# LCD.net
KiCad netlist of a schematic drawn in Altium Designer
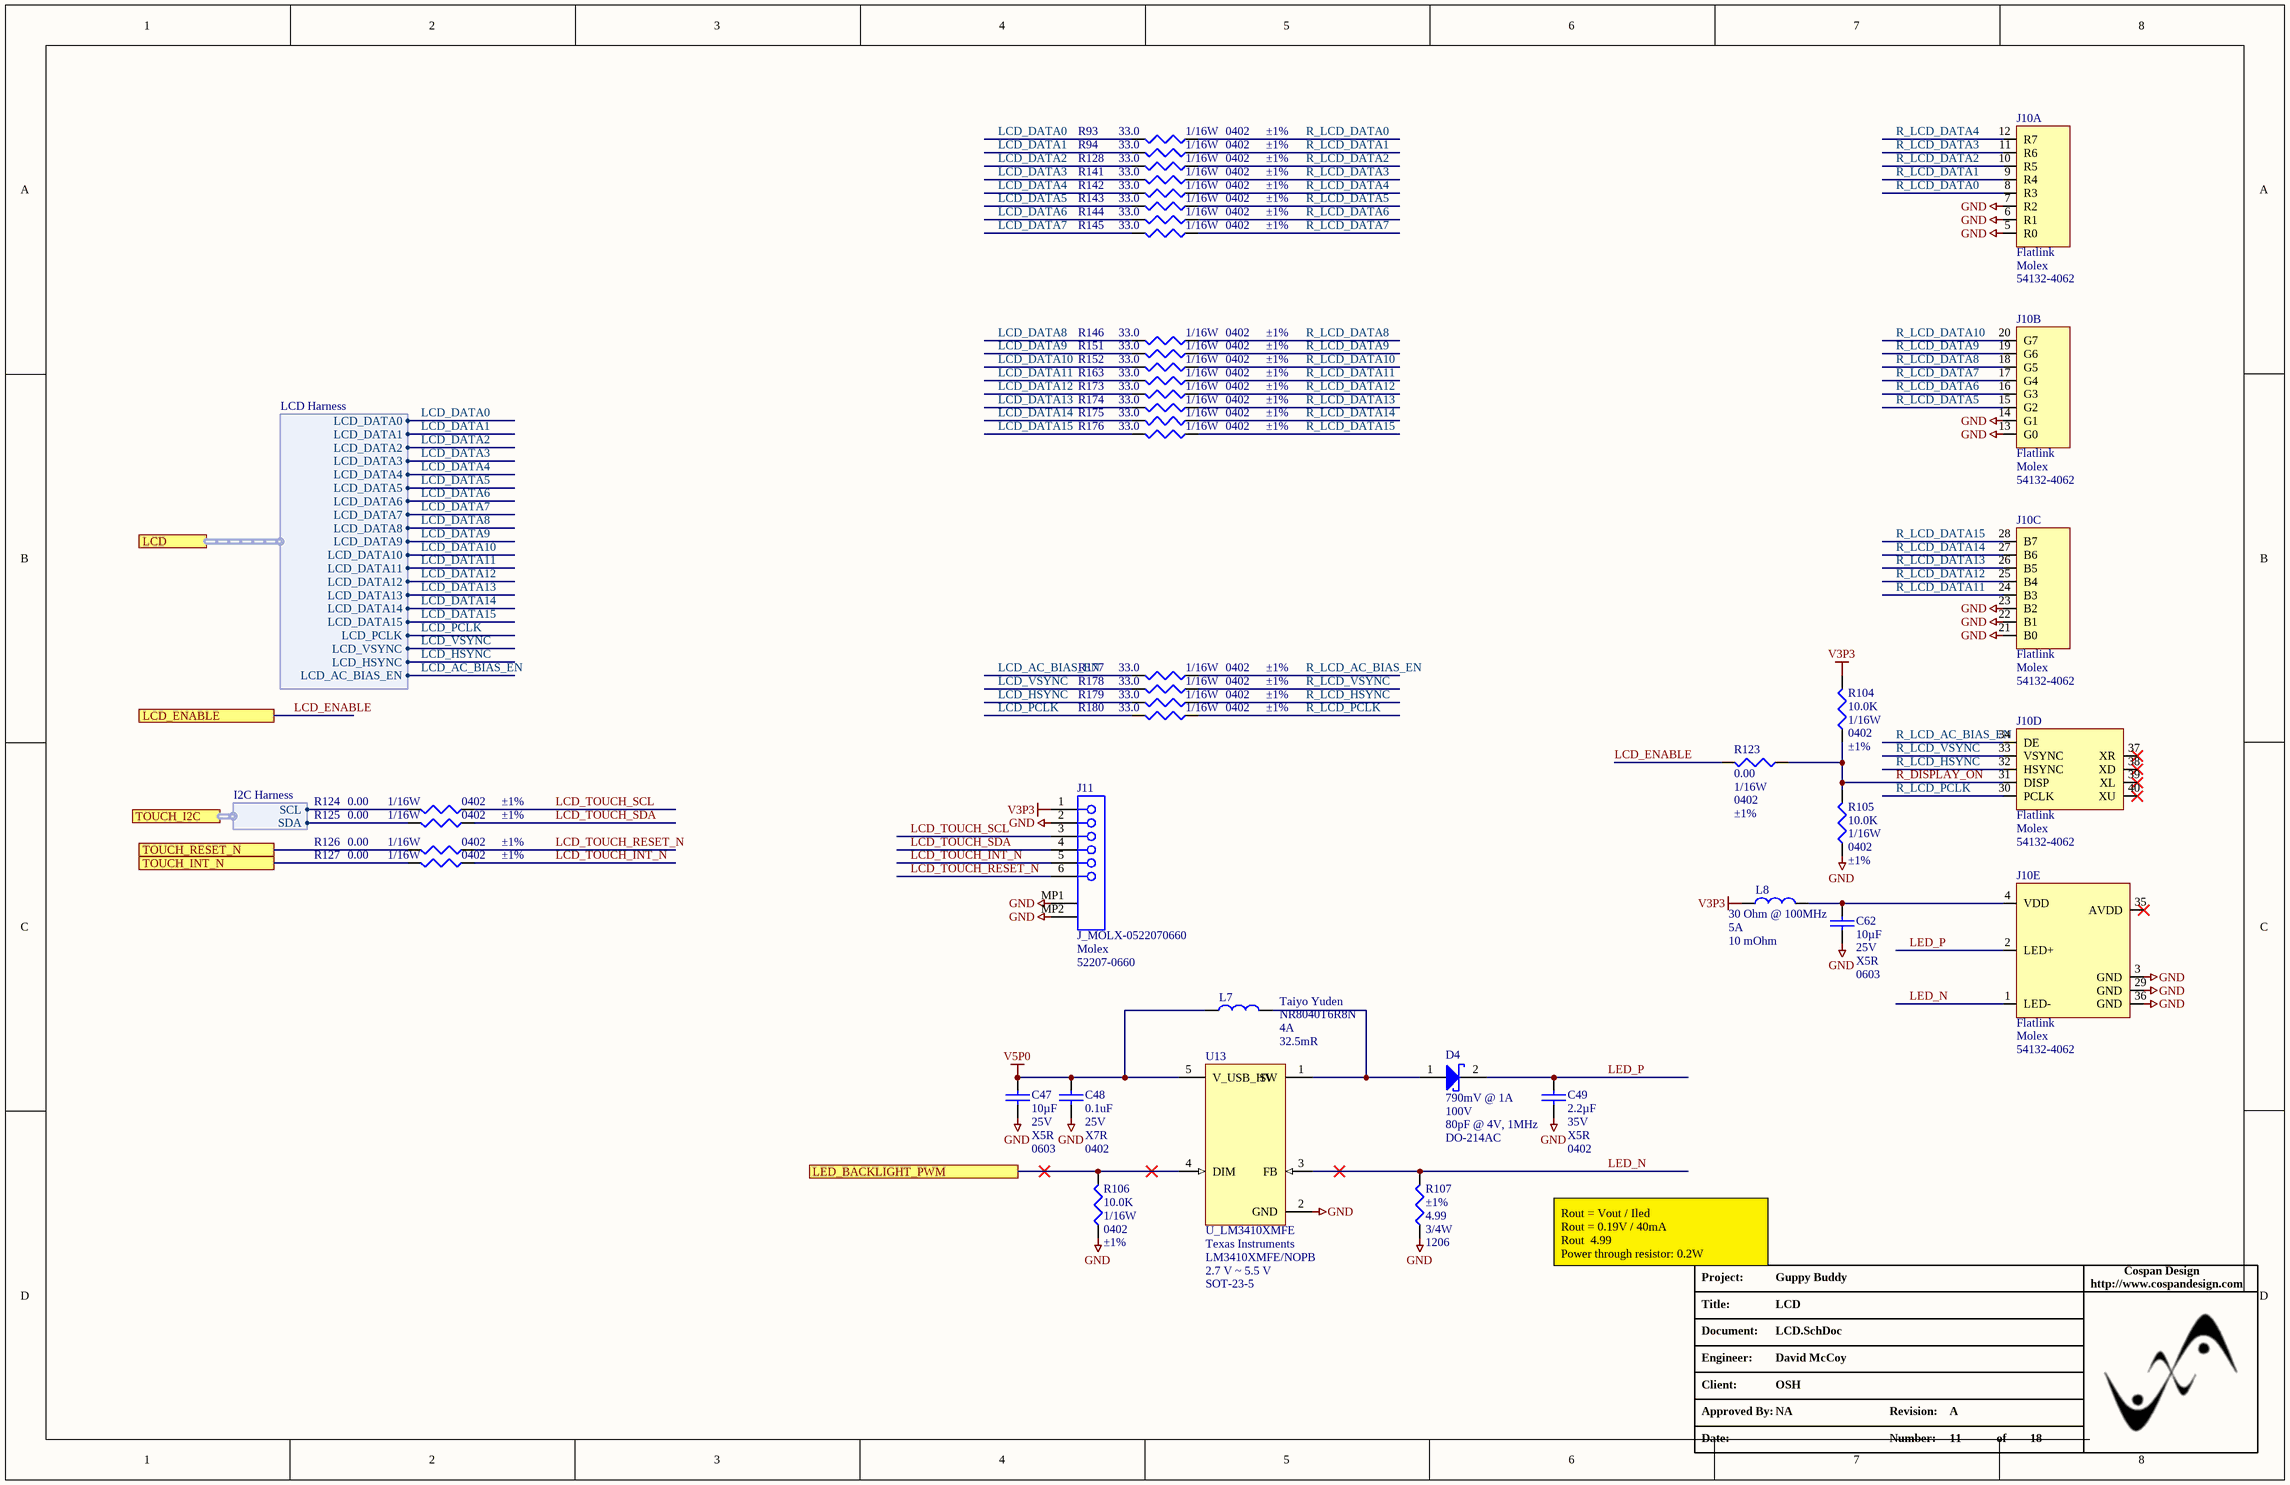
[diagram p0: LCD.SchDoc]

(export (version "E")
  (design (tool "Eeschema 10.0.6"))
  (components
    (comp (ref "C47")
      (value "C_0603_10µF")
      (footprint "C_ERA-0603")
      (description "CAP CER 10UF 16V X5R 0603")
      (fields
        (field (name "CAPACITANCE") "10µF")
        (field (name "VOLTAGE - RATED") "25V")
        (field (name "TEMPERATURE COEFFICIENT") "X5R")
        (field (name "PACKAGE / CASE") "0603")
        (field (name "MANUFACTURER") "Murata Electronics North America")
        (field (name "MANUFACTURER PART NUMBER") "GRM188R61C106MA73D")
      )
      (libsource (lib "Cospan Design") (part "C_0603_10µF"))
    )
    (comp (ref "C48")
      (value "C_0402_0.1UF_25V")
      (footprint "C_0402")
      (description "CAP CER 0.1UF 25V X6S 0402")
      (fields
        (field (name "TOLERANCE") "10%")
        (field (name "CAPACITANCE") "0.1uF")
        (field (name "VOLTAGE - RATED") "25V")
        (field (name "TEMPERATURE COEFFICIENT") "X7R")
        (field (name "PACKAGE / CASE") "0402")
      )
      (libsource (lib "Cospan Design") (part "C_0402_0.1UF_25V"))
    )
    (comp (ref "C49")
      (value "C_0402_2.2uF_35V")
      (footprint "C_0402")
      (description "CAP CER 2.2UF 35V 20% X5R 0402")
      (fields
        (field (name "MANUFACTURER") "TDK Corporation")
        (field (name "MANUFACTURER PART NUMBER") "C1005X5R1V225K050BC")
        (field (name "CAPACITANCE") "2.2µF")
        (field (name "VOLTAGE - RATED") "35V")
        (field (name "TEMPERATURE COEFFICIENT") "X5R")
        (field (name "PACKAGE / CASE") "0402")
      )
      (libsource (lib "Main LibraryX") (part "C_0402_2.2uF_35V"))
    )
    (comp (ref "C62")
      (value "C_0603_10µF")
      (footprint "C_ERA-0603")
      (description "CAP CER 10UF 16V X5R 0603")
      (fields
        (field (name "CAPACITANCE") "10µF")
        (field (name "VOLTAGE - RATED") "25V")
        (field (name "TEMPERATURE COEFFICIENT") "X5R")
        (field (name "PACKAGE / CASE") "0603")
        (field (name "MANUFACTURER") "Murata Electronics North America")
        (field (name "MANUFACTURER PART NUMBER") "GRM188R61C106MA73D")
      )
      (libsource (lib "Cospan Design") (part "C_0603_10µF"))
    )
    (comp (ref "D4")
      (value "B1100-13-F")
      (footprint "DIOM5226X23L")
      (description "DIODE SCHOTTKY 100V 1A SMA")
      (fields
        (field (name "MANUFACTURER") "Diodes Inc")
        (field (name "VOLTAGE - FORWARD (VF) (MAX) @ IF") "790mV @ 1A")
        (field (name "VOLTAGE - DC REVERSE (VR) (MAX)") "100V")
        (field (name "CAPACITANCE @ VR, F") "80pF @ 4V, 1MHz")
        (field (name "PACKAGE / CASE") "DO-214AC")
      )
      (libsource (lib "Main Library") (part "D_SCHOTT_B1100-13-F"))
    )
    (comp (ref "J10")
      (value "Flatlink")
      (footprint "FPC_40PIN_BOTTOM")
      (description "CONN FFC/FPC .50MM 40POS R/A SMD")
      (fields
        (field (name "MANUFACTURER 1") "Molex")
        (field (name "MANUFACTURER PART NUMBER 1") "54132-4062")
      )
      (libsource (lib "Main LibraryX") (part "J_FPC_MOLEX_40POS"))
    )
    (comp (ref "J11")
      (value "J_MOLX-0522070660")
      (footprint "MOLX-52271-0679")
      (description "CONN FFC FPC TOP 6POS 1.00MM R/A")
      (fields
        (field (name "MANUFACTURER 1") "Molex")
        (field (name "MANUFACTURER PART NUMBER 1") "52207-0660")
      )
      (libsource (lib "Main Library") (part "J_MOLX-0522070660"))
    )
    (comp (ref "L7")
      (value "L_6.8µH_SHLD_4A")
      (footprint "IND_TAIYO_NR8040")
      (description "FIXED IND 6.8UH 3.7A 32.5 MOHM")
      (fields
        (field (name "TOLERANCE") "30%")
        (field (name "MANUFACTURER") "Taiyo Yuden")
        (field (name "MANUFACTURER PART NUMBER") "NR8040T6R8N")
        (field (name "MAX DC CURRENT") "4A")
        (field (name "DC RESISTANCE (DCR)") "32.5mR")
      )
      (libsource (lib "Cospan Design") (part "L_6.8µH_SHLD_4A"))
    )
    (comp (ref "L8")
      (value "L_BEAD_0603_30OHM_100MHZ")
      (footprint "R_0603")
      (description "FERRITE BEAD 30 OHM 0603")
      (fields
        (field (name "MANUFACTURER") "TDK Corporation")
        (field (name "MANUFACTURER PART NUMBER") "MPZ1608S300ATAH0")
        (field (name "IMPEDANCE @ FREQUENCY") "30 Ohm @ 100MHz")
        (field (name "CURRENT RATING (MAX)") "5A")
        (field (name "DC RESISTANCE (DCR) (MAX)") "10 mOhm")
      )
      (libsource (lib "Cospan Design") (part "L_BEAD_0603_30OHM_100MHZ"))
    )
    (comp (ref "R93")
      (value "R_0402_33")
      (footprint "R_0402")
      (description "RES 33.0 OHM 1/16W 1% 0402 SMD")
      (fields
        (field (name "MANUFACTURER") "Yageo")
        (field (name "MANUFACTURER PART NUMBER") "RC0402FR-0733RL")
        (field (name "RESISTANCE IN OHMS") "33.0")
        (field (name "POWER (WATTS)") "1/16W")
        (field (name "CASE") "0402")
        (field (name "TOLERANCE") "±1%")
      )
      (libsource (lib "Main Library") (part "R_0402_33"))
    )
    (comp (ref "R94")
      (value "R_0402_33")
      (footprint "R_0402")
      (description "RES 33.0 OHM 1/16W 1% 0402 SMD")
      (fields
        (field (name "MANUFACTURER") "Yageo")
        (field (name "MANUFACTURER PART NUMBER") "RC0402FR-0733RL")
        (field (name "RESISTANCE IN OHMS") "33.0")
        (field (name "POWER (WATTS)") "1/16W")
        (field (name "CASE") "0402")
        (field (name "TOLERANCE") "±1%")
      )
      (libsource (lib "Main Library") (part "R_0402_33"))
    )
    (comp (ref "R104")
      (value "R_0402_10.0K")
      (footprint "R_0402")
      (description "RES 10.0K OHM 1/16W 1% 0402 SMD")
      (fields
        (field (name "MANUFACTURER") "Stackpole Electronics Inc")
        (field (name "MANUFACTURER PART NUMBER") "RMCF0402FT10K0")
        (field (name "RESISTANCE IN OHMS") "10.0K")
        (field (name "POWER (WATTS)") "1/16W")
        (field (name "CASE") "0402")
        (field (name "TOLERANCE") "±1%")
      )
      (libsource (lib "Cospan Design") (part "R_0402_10.0K"))
    )
    (comp (ref "R105")
      (value "R_0402_10.0K")
      (footprint "R_0402")
      (description "RES 10.0K OHM 1/16W 1% 0402 SMD")
      (fields
        (field (name "MANUFACTURER") "Stackpole Electronics Inc")
        (field (name "MANUFACTURER PART NUMBER") "RMCF0402FT10K0")
        (field (name "RESISTANCE IN OHMS") "10.0K")
        (field (name "POWER (WATTS)") "1/16W")
        (field (name "CASE") "0402")
        (field (name "TOLERANCE") "±1%")
      )
      (libsource (lib "Cospan Design") (part "R_0402_10.0K"))
    )
    (comp (ref "R106")
      (value "R_0402_10.0K")
      (footprint "R_0402")
      (description "RES 10.0K OHM 1/16W 1% 0402 SMD")
      (fields
        (field (name "MANUFACTURER") "Stackpole Electronics Inc")
        (field (name "MANUFACTURER PART NUMBER") "RMCF0402FT10K0")
        (field (name "RESISTANCE IN OHMS") "10.0K")
        (field (name "POWER (WATTS)") "1/16W")
        (field (name "CASE") "0402")
        (field (name "TOLERANCE") "±1%")
      )
      (libsource (lib "Cospan Design") (part "R_0402_10.0K"))
    )
    (comp (ref "R107")
      (value "R_1206_4.99")
      (footprint "R_1206")
      (description "RES SMD 4.99 OHM 1% 3/4W 1206")
      (fields
        (field (name "MANUFACTURER") "Vishay / Dale")
        (field (name "MANUFACTURER PART NUMBER") "CRCW12064R99FKEAHP")
        (field (name "TOLERANCE") "±1%")
        (field (name "RESISTANCE IN OHMS") "4.99")
        (field (name "POWER (WATTS)") "3/4W")
        (field (name "CASE") "1206")
      )
      (libsource (lib "Cospan Design") (part "R_1206_4.99"))
    )
    (comp (ref "R123")
      (value "0.0 Ohms")
      (footprint "R_0402")
      (description "RES 0.00 OHM 1/16W 1% 0402 SMD")
      (fields
        (field (name "MANUFACTURER") "Yageo")
        (field (name "MANUFACTURER PART NUMBER") "RC0402JR-070RL")
        (field (name "RESISTANCE IN OHMS") "0.00")
        (field (name "POWER (WATTS)") "1/16W")
        (field (name "CASE") "0402")
        (field (name "TOLERANCE") "±1%")
      )
      (libsource (lib "Cospan Design") (part "R_0402_0.00"))
    )
    (comp (ref "R124")
      (value "0.0 Ohms")
      (footprint "R_0402")
      (description "RES 0.00 OHM 1/16W 1% 0402 SMD")
      (fields
        (field (name "MANUFACTURER") "Yageo")
        (field (name "MANUFACTURER PART NUMBER") "RC0402JR-070RL")
        (field (name "RESISTANCE IN OHMS") "0.00")
        (field (name "POWER (WATTS)") "1/16W")
        (field (name "CASE") "0402")
        (field (name "TOLERANCE") "±1%")
      )
      (libsource (lib "Cospan Design") (part "R_0402_0.00"))
    )
    (comp (ref "R125")
      (value "0.0 Ohms")
      (footprint "R_0402")
      (description "RES 0.00 OHM 1/16W 1% 0402 SMD")
      (fields
        (field (name "MANUFACTURER") "Yageo")
        (field (name "MANUFACTURER PART NUMBER") "RC0402JR-070RL")
        (field (name "RESISTANCE IN OHMS") "0.00")
        (field (name "POWER (WATTS)") "1/16W")
        (field (name "CASE") "0402")
        (field (name "TOLERANCE") "±1%")
      )
      (libsource (lib "Cospan Design") (part "R_0402_0.00"))
    )
    (comp (ref "R126")
      (value "0.0 Ohms")
      (footprint "R_0402")
      (description "RES 0.00 OHM 1/16W 1% 0402 SMD")
      (fields
        (field (name "MANUFACTURER") "Yageo")
        (field (name "MANUFACTURER PART NUMBER") "RC0402JR-070RL")
        (field (name "RESISTANCE IN OHMS") "0.00")
        (field (name "POWER (WATTS)") "1/16W")
        (field (name "CASE") "0402")
        (field (name "TOLERANCE") "±1%")
      )
      (libsource (lib "Cospan Design") (part "R_0402_0.00"))
    )
    (comp (ref "R127")
      (value "0.0 Ohms")
      (footprint "R_0402")
      (description "RES 0.00 OHM 1/16W 1% 0402 SMD")
      (fields
        (field (name "MANUFACTURER") "Yageo")
        (field (name "MANUFACTURER PART NUMBER") "RC0402JR-070RL")
        (field (name "RESISTANCE IN OHMS") "0.00")
        (field (name "POWER (WATTS)") "1/16W")
        (field (name "CASE") "0402")
        (field (name "TOLERANCE") "±1%")
      )
      (libsource (lib "Cospan Design") (part "R_0402_0.00"))
    )
    (comp (ref "R128")
      (value "R_0402_33")
      (footprint "R_0402")
      (description "RES 33.0 OHM 1/16W 1% 0402 SMD")
      (fields
        (field (name "MANUFACTURER") "Yageo")
        (field (name "MANUFACTURER PART NUMBER") "RC0402FR-0733RL")
        (field (name "RESISTANCE IN OHMS") "33.0")
        (field (name "POWER (WATTS)") "1/16W")
        (field (name "CASE") "0402")
        (field (name "TOLERANCE") "±1%")
      )
      (libsource (lib "Main Library") (part "R_0402_33"))
    )
    (comp (ref "R141")
      (value "R_0402_33")
      (footprint "R_0402")
      (description "RES 33.0 OHM 1/16W 1% 0402 SMD")
      (fields
        (field (name "MANUFACTURER") "Yageo")
        (field (name "MANUFACTURER PART NUMBER") "RC0402FR-0733RL")
        (field (name "RESISTANCE IN OHMS") "33.0")
        (field (name "POWER (WATTS)") "1/16W")
        (field (name "CASE") "0402")
        (field (name "TOLERANCE") "±1%")
      )
      (libsource (lib "Main Library") (part "R_0402_33"))
    )
    (comp (ref "R142")
      (value "R_0402_33")
      (footprint "R_0402")
      (description "RES 33.0 OHM 1/16W 1% 0402 SMD")
      (fields
        (field (name "MANUFACTURER") "Yageo")
        (field (name "MANUFACTURER PART NUMBER") "RC0402FR-0733RL")
        (field (name "RESISTANCE IN OHMS") "33.0")
        (field (name "POWER (WATTS)") "1/16W")
        (field (name "CASE") "0402")
        (field (name "TOLERANCE") "±1%")
      )
      (libsource (lib "Main Library") (part "R_0402_33"))
    )
    (comp (ref "R143")
      (value "R_0402_33")
      (footprint "R_0402")
      (description "RES 33.0 OHM 1/16W 1% 0402 SMD")
      (fields
        (field (name "MANUFACTURER") "Yageo")
        (field (name "MANUFACTURER PART NUMBER") "RC0402FR-0733RL")
        (field (name "RESISTANCE IN OHMS") "33.0")
        (field (name "POWER (WATTS)") "1/16W")
        (field (name "CASE") "0402")
        (field (name "TOLERANCE") "±1%")
      )
      (libsource (lib "Main Library") (part "R_0402_33"))
    )
    (comp (ref "R144")
      (value "R_0402_33")
      (footprint "R_0402")
      (description "RES 33.0 OHM 1/16W 1% 0402 SMD")
      (fields
        (field (name "MANUFACTURER") "Yageo")
        (field (name "MANUFACTURER PART NUMBER") "RC0402FR-0733RL")
        (field (name "RESISTANCE IN OHMS") "33.0")
        (field (name "POWER (WATTS)") "1/16W")
        (field (name "CASE") "0402")
        (field (name "TOLERANCE") "±1%")
      )
      (libsource (lib "Main Library") (part "R_0402_33"))
    )
    (comp (ref "R145")
      (value "R_0402_33")
      (footprint "R_0402")
      (description "RES 33.0 OHM 1/16W 1% 0402 SMD")
      (fields
        (field (name "MANUFACTURER") "Yageo")
        (field (name "MANUFACTURER PART NUMBER") "RC0402FR-0733RL")
        (field (name "RESISTANCE IN OHMS") "33.0")
        (field (name "POWER (WATTS)") "1/16W")
        (field (name "CASE") "0402")
        (field (name "TOLERANCE") "±1%")
      )
      (libsource (lib "Main Library") (part "R_0402_33"))
    )
    (comp (ref "R146")
      (value "R_0402_33")
      (footprint "R_0402")
      (description "RES 33.0 OHM 1/16W 1% 0402 SMD")
      (fields
        (field (name "MANUFACTURER") "Yageo")
        (field (name "MANUFACTURER PART NUMBER") "RC0402FR-0733RL")
        (field (name "RESISTANCE IN OHMS") "33.0")
        (field (name "POWER (WATTS)") "1/16W")
        (field (name "CASE") "0402")
        (field (name "TOLERANCE") "±1%")
      )
      (libsource (lib "Main Library") (part "R_0402_33"))
    )
    (comp (ref "R151")
      (value "R_0402_33")
      (footprint "R_0402")
      (description "RES 33.0 OHM 1/16W 1% 0402 SMD")
      (fields
        (field (name "MANUFACTURER") "Yageo")
        (field (name "MANUFACTURER PART NUMBER") "RC0402FR-0733RL")
        (field (name "RESISTANCE IN OHMS") "33.0")
        (field (name "POWER (WATTS)") "1/16W")
        (field (name "CASE") "0402")
        (field (name "TOLERANCE") "±1%")
      )
      (libsource (lib "Main Library") (part "R_0402_33"))
    )
    (comp (ref "R152")
      (value "R_0402_33")
      (footprint "R_0402")
      (description "RES 33.0 OHM 1/16W 1% 0402 SMD")
      (fields
        (field (name "MANUFACTURER") "Yageo")
        (field (name "MANUFACTURER PART NUMBER") "RC0402FR-0733RL")
        (field (name "RESISTANCE IN OHMS") "33.0")
        (field (name "POWER (WATTS)") "1/16W")
        (field (name "CASE") "0402")
        (field (name "TOLERANCE") "±1%")
      )
      (libsource (lib "Main Library") (part "R_0402_33"))
    )
    (comp (ref "R163")
      (value "R_0402_33")
      (footprint "R_0402")
      (description "RES 33.0 OHM 1/16W 1% 0402 SMD")
      (fields
        (field (name "MANUFACTURER") "Yageo")
        (field (name "MANUFACTURER PART NUMBER") "RC0402FR-0733RL")
        (field (name "RESISTANCE IN OHMS") "33.0")
        (field (name "POWER (WATTS)") "1/16W")
        (field (name "CASE") "0402")
        (field (name "TOLERANCE") "±1%")
      )
      (libsource (lib "Main Library") (part "R_0402_33"))
    )
    (comp (ref "R173")
      (value "R_0402_33")
      (footprint "R_0402")
      (description "RES 33.0 OHM 1/16W 1% 0402 SMD")
      (fields
        (field (name "MANUFACTURER") "Yageo")
        (field (name "MANUFACTURER PART NUMBER") "RC0402FR-0733RL")
        (field (name "RESISTANCE IN OHMS") "33.0")
        (field (name "POWER (WATTS)") "1/16W")
        (field (name "CASE") "0402")
        (field (name "TOLERANCE") "±1%")
      )
      (libsource (lib "Main Library") (part "R_0402_33"))
    )
    (comp (ref "R174")
      (value "R_0402_33")
      (footprint "R_0402")
      (description "RES 33.0 OHM 1/16W 1% 0402 SMD")
      (fields
        (field (name "MANUFACTURER") "Yageo")
        (field (name "MANUFACTURER PART NUMBER") "RC0402FR-0733RL")
        (field (name "RESISTANCE IN OHMS") "33.0")
        (field (name "POWER (WATTS)") "1/16W")
        (field (name "CASE") "0402")
        (field (name "TOLERANCE") "±1%")
      )
      (libsource (lib "Main Library") (part "R_0402_33"))
    )
    (comp (ref "R175")
      (value "R_0402_33")
      (footprint "R_0402")
      (description "RES 33.0 OHM 1/16W 1% 0402 SMD")
      (fields
        (field (name "MANUFACTURER") "Yageo")
        (field (name "MANUFACTURER PART NUMBER") "RC0402FR-0733RL")
        (field (name "RESISTANCE IN OHMS") "33.0")
        (field (name "POWER (WATTS)") "1/16W")
        (field (name "CASE") "0402")
        (field (name "TOLERANCE") "±1%")
      )
      (libsource (lib "Main Library") (part "R_0402_33"))
    )
    (comp (ref "R176")
      (value "R_0402_33")
      (footprint "R_0402")
      (description "RES 33.0 OHM 1/16W 1% 0402 SMD")
      (fields
        (field (name "MANUFACTURER") "Yageo")
        (field (name "MANUFACTURER PART NUMBER") "RC0402FR-0733RL")
        (field (name "RESISTANCE IN OHMS") "33.0")
        (field (name "POWER (WATTS)") "1/16W")
        (field (name "CASE") "0402")
        (field (name "TOLERANCE") "±1%")
      )
      (libsource (lib "Main Library") (part "R_0402_33"))
    )
    (comp (ref "R177")
      (value "R_0402_33")
      (footprint "R_0402")
      (description "RES 33.0 OHM 1/16W 1% 0402 SMD")
      (fields
        (field (name "MANUFACTURER") "Yageo")
        (field (name "MANUFACTURER PART NUMBER") "RC0402FR-0733RL")
        (field (name "RESISTANCE IN OHMS") "33.0")
        (field (name "POWER (WATTS)") "1/16W")
        (field (name "CASE") "0402")
        (field (name "TOLERANCE") "±1%")
      )
      (libsource (lib "Main Library") (part "R_0402_33"))
    )
    (comp (ref "R178")
      (value "R_0402_33")
      (footprint "R_0402")
      (description "RES 33.0 OHM 1/16W 1% 0402 SMD")
      (fields
        (field (name "MANUFACTURER") "Yageo")
        (field (name "MANUFACTURER PART NUMBER") "RC0402FR-0733RL")
        (field (name "RESISTANCE IN OHMS") "33.0")
        (field (name "POWER (WATTS)") "1/16W")
        (field (name "CASE") "0402")
        (field (name "TOLERANCE") "±1%")
      )
      (libsource (lib "Main Library") (part "R_0402_33"))
    )
    (comp (ref "R179")
      (value "R_0402_33")
      (footprint "R_0402")
      (description "RES 33.0 OHM 1/16W 1% 0402 SMD")
      (fields
        (field (name "MANUFACTURER") "Yageo")
        (field (name "MANUFACTURER PART NUMBER") "RC0402FR-0733RL")
        (field (name "RESISTANCE IN OHMS") "33.0")
        (field (name "POWER (WATTS)") "1/16W")
        (field (name "CASE") "0402")
        (field (name "TOLERANCE") "±1%")
      )
      (libsource (lib "Main Library") (part "R_0402_33"))
    )
    (comp (ref "R180")
      (value "R_0402_33")
      (footprint "R_0402")
      (description "RES 33.0 OHM 1/16W 1% 0402 SMD")
      (fields
        (field (name "MANUFACTURER") "Yageo")
        (field (name "MANUFACTURER PART NUMBER") "RC0402FR-0733RL")
        (field (name "RESISTANCE IN OHMS") "33.0")
        (field (name "POWER (WATTS)") "1/16W")
        (field (name "CASE") "0402")
        (field (name "TOLERANCE") "±1%")
      )
      (libsource (lib "Main Library") (part "R_0402_33"))
    )
    (comp (ref "U13")
      (value "U_LM3410XMFE")
      (footprint "MF05A_N")
      (description "IC DRVR WT/OLED BCKLT SOT23-5")
      (fields
        (field (name "MANUFACTURER") "Texas Instruments")
        (field (name "MANUFACTURER PART NUMBER") "LM3410XMFE/NOPB")
        (field (name "VOLTAGE - SUPPLY") "2.7 V ~ 5.5 V")
        (field (name "SUPPLIER DEVICE PACKAGE") "SOT-23-5")
      )
      (libsource (lib "Main Library") (part "U_LM3410XMFE"))
    )
  )
  (nets
    (net (code "4") (name "/LCD_AC_BIAS_EN") (class "Default")
      (node (ref "R177") (pin "1") (pinfunction "1_1") (pintype "passive"))
    )
    (net (code "5") (name "/LCD_DATA0") (class "Default")
      (node (ref "R93") (pin "1") (pinfunction "1_1") (pintype "passive"))
    )
    (net (code "6") (name "/LCD_DATA1") (class "Default")
      (node (ref "R94") (pin "1") (pinfunction "1_1") (pintype "passive"))
    )
    (net (code "7") (name "/LCD_DATA2") (class "Default")
      (node (ref "R128") (pin "1") (pinfunction "1_1") (pintype "passive"))
    )
    (net (code "8") (name "/LCD_DATA3") (class "Default")
      (node (ref "R141") (pin "1") (pinfunction "1_1") (pintype "passive"))
    )
    (net (code "9") (name "/LCD_DATA4") (class "Default")
      (node (ref "R142") (pin "1") (pinfunction "1_1") (pintype "passive"))
    )
    (net (code "10") (name "/LCD_DATA5") (class "Default")
      (node (ref "R143") (pin "1") (pinfunction "1_1") (pintype "passive"))
    )
    (net (code "11") (name "/LCD_DATA6") (class "Default")
      (node (ref "R144") (pin "1") (pinfunction "1_1") (pintype "passive"))
    )
    (net (code "12") (name "/LCD_DATA7") (class "Default")
      (node (ref "R145") (pin "1") (pinfunction "1_1") (pintype "passive"))
    )
    (net (code "13") (name "/LCD_DATA8") (class "Default")
      (node (ref "R146") (pin "1") (pinfunction "1_1") (pintype "passive"))
    )
    (net (code "14") (name "/LCD_DATA9") (class "Default")
      (node (ref "R151") (pin "1") (pinfunction "1_1") (pintype "passive"))
    )
    (net (code "15") (name "/LCD_DATA10") (class "Default")
      (node (ref "R152") (pin "1") (pinfunction "1_1") (pintype "passive"))
    )
    (net (code "16") (name "/LCD_DATA11") (class "Default")
      (node (ref "R163") (pin "1") (pinfunction "1_1") (pintype "passive"))
    )
    (net (code "17") (name "/LCD_DATA12") (class "Default")
      (node (ref "R173") (pin "1") (pinfunction "1_1") (pintype "passive"))
    )
    (net (code "18") (name "/LCD_DATA13") (class "Default")
      (node (ref "R174") (pin "1") (pinfunction "1_1") (pintype "passive"))
    )
    (net (code "19") (name "/LCD_DATA14") (class "Default")
      (node (ref "R175") (pin "1") (pinfunction "1_1") (pintype "passive"))
    )
    (net (code "20") (name "/LCD_DATA15") (class "Default")
      (node (ref "R176") (pin "1") (pinfunction "1_1") (pintype "passive"))
    )
    (net (code "21") (name "/LCD_ENABLE") (class "Default")
      (node (ref "R123") (pin "1") (pinfunction "1_1") (pintype "passive"))
    )
    (net (code "22") (name "/LCD_HSYNC") (class "Default")
      (node (ref "R179") (pin "1") (pinfunction "1_1") (pintype "passive"))
    )
    (net (code "23") (name "/LCD_PCLK") (class "Default")
      (node (ref "R180") (pin "1") (pinfunction "1_1") (pintype "passive"))
    )
    (net (code "24") (name "/LCD_TOUCH_INT_N") (class "Default")
      (node (ref "J11") (pin "5") (pinfunction "5_5") (pintype "passive"))
      (node (ref "R127") (pin "2") (pinfunction "2_2") (pintype "passive"))
    )
    (net (code "25") (name "/LCD_TOUCH_RESET_N") (class "Default")
      (node (ref "J11") (pin "6") (pinfunction "6_6") (pintype "passive"))
      (node (ref "R126") (pin "2") (pinfunction "2_2") (pintype "passive"))
    )
    (net (code "26") (name "/LCD_TOUCH_SCL") (class "Default")
      (node (ref "J11") (pin "3") (pinfunction "3_3") (pintype "passive"))
      (node (ref "R124") (pin "2") (pinfunction "2_2") (pintype "passive"))
    )
    (net (code "27") (name "/LCD_TOUCH_SDA") (class "Default")
      (node (ref "J11") (pin "4") (pinfunction "4_4") (pintype "passive"))
      (node (ref "R125") (pin "2") (pinfunction "2_2") (pintype "passive"))
    )
    (net (code "28") (name "/LCD_VSYNC") (class "Default")
      (node (ref "R178") (pin "1") (pinfunction "1_1") (pintype "passive"))
    )
    (net (code "29") (name "/LED_BACKLIGHT_PWM") (class "Default")
      (node (ref "R106") (pin "1") (pinfunction "1_1") (pintype "passive"))
      (node (ref "U13") (pin "4") (pinfunction "DIM_4") (pintype "input"))
    )
    (net (code "30") (name "/LED_N") (class "Default")
      (node (ref "J10") (pin "1") (pinfunction "LED-_1") (pintype "passive"))
      (node (ref "R107") (pin "1") (pinfunction "1_1") (pintype "passive"))
      (node (ref "U13") (pin "3") (pinfunction "FB_3") (pintype "input"))
    )
    (net (code "31") (name "/LED_P") (class "Default")
      (node (ref "C49") (pin "2") (pinfunction "2_2") (pintype "passive"))
      (node (ref "D4") (pin "2") (pinfunction "K_2") (pintype "passive"))
      (node (ref "J10") (pin "2") (pinfunction "LED+_2") (pintype "passive"))
    )
    (net (code "32") (name "/R_DISPLAY_ON") (class "Default")
      (node (ref "J10") (pin "31") (pinfunction "DISP_31") (pintype "passive"))
      (node (ref "R104") (pin "2") (pinfunction "2_2") (pintype "passive"))
      (node (ref "R105") (pin "1") (pinfunction "1_1") (pintype "passive"))
      (node (ref "R123") (pin "2") (pinfunction "2_2") (pintype "passive"))
    )
    (net (code "33") (name "/R_LCD_AC_BIAS_EN") (class "Default")
      (node (ref "J10") (pin "34") (pinfunction "DE_34") (pintype "passive"))
      (node (ref "R177") (pin "2") (pinfunction "2_2") (pintype "passive"))
    )
    (net (code "34") (name "/R_LCD_DATA0") (class "Default")
      (node (ref "J10") (pin "8") (pinfunction "R3_8") (pintype "passive"))
      (node (ref "R93") (pin "2") (pinfunction "2_2") (pintype "passive"))
    )
    (net (code "35") (name "/R_LCD_DATA1") (class "Default")
      (node (ref "J10") (pin "9") (pinfunction "R4_9") (pintype "passive"))
      (node (ref "R94") (pin "2") (pinfunction "2_2") (pintype "passive"))
    )
    (net (code "36") (name "/R_LCD_DATA2") (class "Default")
      (node (ref "J10") (pin "10") (pinfunction "R5_10") (pintype "passive"))
      (node (ref "R128") (pin "2") (pinfunction "2_2") (pintype "passive"))
    )
    (net (code "37") (name "/R_LCD_DATA3") (class "Default")
      (node (ref "J10") (pin "11") (pinfunction "R6_11") (pintype "passive"))
      (node (ref "R141") (pin "2") (pinfunction "2_2") (pintype "passive"))
    )
    (net (code "38") (name "/R_LCD_DATA4") (class "Default")
      (node (ref "J10") (pin "12") (pinfunction "R7_12") (pintype "passive"))
      (node (ref "R142") (pin "2") (pinfunction "2_2") (pintype "passive"))
    )
    (net (code "39") (name "/R_LCD_DATA5") (class "Default")
      (node (ref "J10") (pin "15") (pinfunction "G2_15") (pintype "passive"))
      (node (ref "R143") (pin "2") (pinfunction "2_2") (pintype "passive"))
    )
    (net (code "40") (name "/R_LCD_DATA6") (class "Default")
      (node (ref "J10") (pin "16") (pinfunction "G3_16") (pintype "passive"))
      (node (ref "R144") (pin "2") (pinfunction "2_2") (pintype "passive"))
    )
    (net (code "41") (name "/R_LCD_DATA7") (class "Default")
      (node (ref "J10") (pin "17") (pinfunction "G4_17") (pintype "passive"))
      (node (ref "R145") (pin "2") (pinfunction "2_2") (pintype "passive"))
    )
    (net (code "42") (name "/R_LCD_DATA8") (class "Default")
      (node (ref "J10") (pin "18") (pinfunction "G5_18") (pintype "passive"))
      (node (ref "R146") (pin "2") (pinfunction "2_2") (pintype "passive"))
    )
    (net (code "43") (name "/R_LCD_DATA9") (class "Default")
      (node (ref "J10") (pin "19") (pinfunction "G6_19") (pintype "passive"))
      (node (ref "R151") (pin "2") (pinfunction "2_2") (pintype "passive"))
    )
    (net (code "44") (name "/R_LCD_DATA10") (class "Default")
      (node (ref "J10") (pin "20") (pinfunction "G7_20") (pintype "passive"))
      (node (ref "R152") (pin "2") (pinfunction "2_2") (pintype "passive"))
    )
    (net (code "45") (name "/R_LCD_DATA11") (class "Default")
      (node (ref "J10") (pin "24") (pinfunction "B3_24") (pintype "passive"))
      (node (ref "R163") (pin "2") (pinfunction "2_2") (pintype "passive"))
    )
    (net (code "46") (name "/R_LCD_DATA12") (class "Default")
      (node (ref "J10") (pin "25") (pinfunction "B4_25") (pintype "passive"))
      (node (ref "R173") (pin "2") (pinfunction "2_2") (pintype "passive"))
    )
    (net (code "47") (name "/R_LCD_DATA13") (class "Default")
      (node (ref "J10") (pin "26") (pinfunction "B5_26") (pintype "passive"))
      (node (ref "R174") (pin "2") (pinfunction "2_2") (pintype "passive"))
    )
    (net (code "48") (name "/R_LCD_DATA14") (class "Default")
      (node (ref "J10") (pin "27") (pinfunction "B6_27") (pintype "passive"))
      (node (ref "R175") (pin "2") (pinfunction "2_2") (pintype "passive"))
    )
    (net (code "49") (name "/R_LCD_DATA15") (class "Default")
      (node (ref "J10") (pin "28") (pinfunction "B7_28") (pintype "passive"))
      (node (ref "R176") (pin "2") (pinfunction "2_2") (pintype "passive"))
    )
    (net (code "50") (name "/R_LCD_HSYNC") (class "Default")
      (node (ref "J10") (pin "32") (pinfunction "HSYNC_32") (pintype "passive"))
      (node (ref "R179") (pin "2") (pinfunction "2_2") (pintype "passive"))
    )
    (net (code "51") (name "/R_LCD_PCLK") (class "Default")
      (node (ref "J10") (pin "30") (pinfunction "PCLK_30") (pintype "passive"))
      (node (ref "R180") (pin "2") (pinfunction "2_2") (pintype "passive"))
    )
    (net (code "52") (name "/R_LCD_VSYNC") (class "Default")
      (node (ref "J10") (pin "33") (pinfunction "VSYNC_33") (pintype "passive"))
      (node (ref "R178") (pin "2") (pinfunction "2_2") (pintype "passive"))
    )
    (net (code "53") (name "/SCL") (class "Default")
      (node (ref "R124") (pin "1") (pinfunction "1_1") (pintype "passive"))
    )
    (net (code "54") (name "/SDA") (class "Default")
      (node (ref "R125") (pin "1") (pinfunction "1_1") (pintype "passive"))
    )
    (net (code "55") (name "/TOUCH_INT_N") (class "Default")
      (node (ref "R127") (pin "1") (pinfunction "1_1") (pintype "passive"))
    )
    (net (code "56") (name "/TOUCH_RESET_N") (class "Default")
      (node (ref "R126") (pin "1") (pinfunction "1_1") (pintype "passive"))
    )
    (net (code "59") (name "GND") (class "Default")
      (node (ref "C47") (pin "1") (pinfunction "1_1") (pintype "passive"))
      (node (ref "C48") (pin "1") (pinfunction "1_1") (pintype "passive"))
      (node (ref "C49") (pin "1") (pinfunction "1_1") (pintype "passive"))
      (node (ref "C62") (pin "1") (pinfunction "1_1") (pintype "passive"))
      (node (ref "J10") (pin "13") (pinfunction "G0_13") (pintype "passive"))
      (node (ref "J10") (pin "14") (pinfunction "G1_14") (pintype "passive"))
      (node (ref "J10") (pin "21") (pinfunction "B0_21") (pintype "passive"))
      (node (ref "J10") (pin "22") (pinfunction "B1_22") (pintype "passive"))
      (node (ref "J10") (pin "23") (pinfunction "B2_23") (pintype "passive"))
      (node (ref "J10") (pin "29") (pinfunction "GND_29") (pintype "passive"))
      (node (ref "J10") (pin "3") (pinfunction "GND_3") (pintype "passive"))
      (node (ref "J10") (pin "36") (pinfunction "GND_36") (pintype "passive"))
      (node (ref "J10") (pin "5") (pinfunction "R0_5") (pintype "passive"))
      (node (ref "J10") (pin "6") (pinfunction "R1_6") (pintype "passive"))
      (node (ref "J10") (pin "7") (pinfunction "R2_7") (pintype "passive"))
      (node (ref "J11") (pin "2") (pinfunction "2_2") (pintype "passive"))
      (node (ref "J11") (pin "MP1") (pinfunction "MP1_MP1") (pintype "passive"))
      (node (ref "J11") (pin "MP2") (pinfunction "MP2_MP2") (pintype "passive"))
      (node (ref "R105") (pin "2") (pinfunction "2_2") (pintype "passive"))
      (node (ref "R106") (pin "2") (pinfunction "2_2") (pintype "passive"))
      (node (ref "R107") (pin "2") (pinfunction "2_2") (pintype "passive"))
      (node (ref "U13") (pin "2") (pinfunction "GND_2") (pintype "power_in"))
    )
    (net (code "60") (name "Net-(D4-A)") (class "Default")
      (node (ref "D4") (pin "1") (pinfunction "A_1") (pintype "passive"))
      (node (ref "L7") (pin "2") (pintype "passive"))
      (node (ref "U13") (pin "1") (pinfunction "SW_1") (pintype "power_in"))
    )
    (net (code "61") (name "Net-(J10E-VDD)") (class "Default")
      (node (ref "C62") (pin "2") (pinfunction "2_2") (pintype "passive"))
      (node (ref "J10") (pin "4") (pinfunction "VDD_4") (pintype "passive"))
      (node (ref "L8") (pin "1") (pintype "passive"))
    )
    (net (code "62") (name "V3P3") (class "Default")
      (node (ref "J11") (pin "1") (pinfunction "1_1") (pintype "passive"))
      (node (ref "L8") (pin "2") (pintype "passive"))
      (node (ref "R104") (pin "1") (pinfunction "1_1") (pintype "passive"))
    )
    (net (code "63") (name "V5P0") (class "Default")
      (node (ref "C47") (pin "2") (pinfunction "2_2") (pintype "passive"))
      (node (ref "C48") (pin "2") (pinfunction "2_2") (pintype "passive"))
      (node (ref "L7") (pin "1") (pintype "passive"))
      (node (ref "U13") (pin "5") (pinfunction "V_USB_HV_5") (pintype "power_in"))
    )
    (net (code "64") (name "unconnected-(J10D-XD-Pad38)") (class "Default")
      (node (ref "J10") (pin "38") (pinfunction "XD_38") (pintype "passive+no_connect"))
    )
    (net (code "65") (name "unconnected-(J10D-XL-Pad39)") (class "Default")
      (node (ref "J10") (pin "39") (pinfunction "XL_39") (pintype "passive+no_connect"))
    )
    (net (code "66") (name "unconnected-(J10D-XR-Pad37)") (class "Default")
      (node (ref "J10") (pin "37") (pinfunction "XR_37") (pintype "passive+no_connect"))
    )
    (net (code "67") (name "unconnected-(J10D-XU-Pad40)") (class "Default")
      (node (ref "J10") (pin "40") (pinfunction "XU_40") (pintype "passive+no_connect"))
    )
    (net (code "68") (name "unconnected-(J10E-AVDD-Pad35)") (class "Default")
      (node (ref "J10") (pin "35") (pinfunction "AVDD_35") (pintype "passive+no_connect"))
    )
  )
)
